# EasyDriver_v45.net
KiCad netlist of a schematic drawn in EAGLE
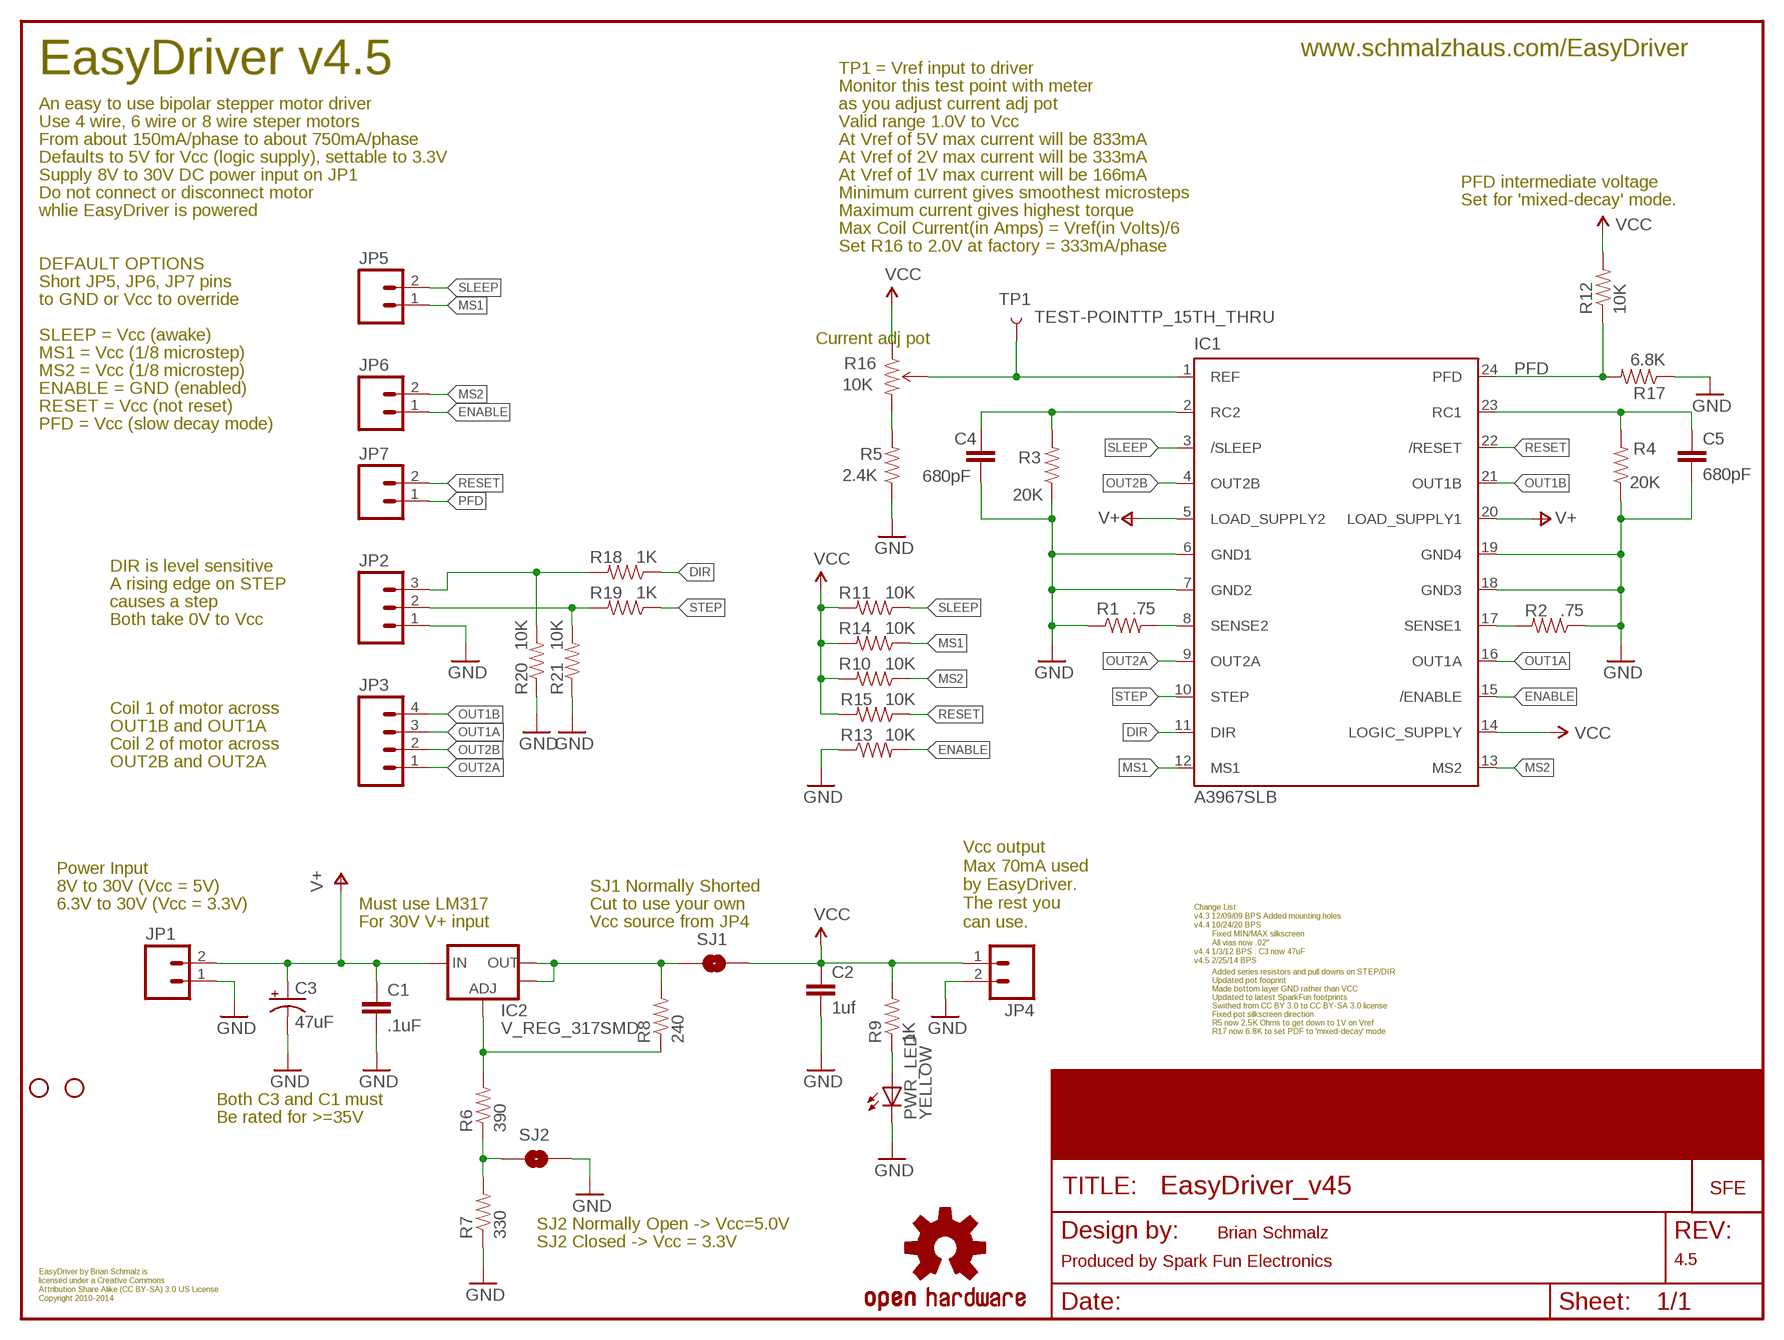
[diagram p0: schematic, sheet 1]

(export (version "E")
  (design (tool "Eeschema 10.0.6"))
  (components
    (comp (ref "C1")
      (value ".1uF")
      (footprint "eagle-import:0603-CAP")
      (libsource (lib "eagle-import") (part "CAP0603-CAP"))
    )
    (comp (ref "C2")
      (value "1uf")
      (footprint "eagle-import:0603-CAP")
      (libsource (lib "eagle-import") (part "CAP0603-CAP"))
    )
    (comp (ref "C3")
      (value "47uF")
      (footprint "eagle-import:PANASONIC_D")
      (libsource (lib "eagle-import") (part "CPOL-USD"))
    )
    (comp (ref "C4")
      (value "680pF")
      (footprint "eagle-import:0603-CAP")
      (libsource (lib "eagle-import") (part "CAP0603-CAP"))
    )
    (comp (ref "C5")
      (value "680pF")
      (footprint "eagle-import:0603-CAP")
      (libsource (lib "eagle-import") (part "CAP0603-CAP"))
    )
    (comp (ref "FRAME2")
      (value "FRAME-LETTER")
      (footprint "eagle-import:CREATIVE_COMMONS")
      (libsource (lib "eagle-import") (part "FRAME-LETTER"))
    )
    (comp (ref "IC1")
      (value "A3967SLB")
      (footprint "eagle-import:SO24W")
      (libsource (lib "eagle-import") (part "A3967SLB"))
    )
    (comp (ref "IC2")
      (value "V_REG_317SMD")
      (footprint "eagle-import:SOT223")
      (libsource (lib "eagle-import") (part "V_REG_317SMD"))
    )
    (comp (ref "JP1")
      (value "M021X02_NO_SILK")
      (footprint "eagle-import:1X02_NO_SILK")
      (libsource (lib "eagle-import") (part "M021X02_NO_SILK"))
    )
    (comp (ref "JP2")
      (value "M031X03_NO_SILK")
      (footprint "eagle-import:1X03_NO_SILK")
      (libsource (lib "eagle-import") (part "M031X03_NO_SILK"))
    )
    (comp (ref "JP3")
      (value "M041X04_NO_SILK")
      (footprint "eagle-import:1X04_NO_SILK")
      (libsource (lib "eagle-import") (part "M041X04_NO_SILK"))
    )
    (comp (ref "JP4")
      (value "M021X02_NO_SILK")
      (footprint "eagle-import:1X02_NO_SILK")
      (libsource (lib "eagle-import") (part "M021X02_NO_SILK"))
    )
    (comp (ref "JP5")
      (value "M021X02_NO_SILK")
      (footprint "eagle-import:1X02_NO_SILK")
      (libsource (lib "eagle-import") (part "M021X02_NO_SILK"))
    )
    (comp (ref "JP6")
      (value "M021X02_NO_SILK")
      (footprint "eagle-import:1X02_NO_SILK")
      (libsource (lib "eagle-import") (part "M021X02_NO_SILK"))
    )
    (comp (ref "JP7")
      (value "M021X02_NO_SILK")
      (footprint "eagle-import:1X02_NO_SILK")
      (libsource (lib "eagle-import") (part "M021X02_NO_SILK"))
    )
    (comp (ref "JP8")
      (value "STAND-OFF")
      (footprint "eagle-import:STAND-OFF")
      (libsource (lib "eagle-import") (part "STAND-OFF"))
    )
    (comp (ref "JP9")
      (value "STAND-OFF")
      (footprint "eagle-import:STAND-OFF")
      (libsource (lib "eagle-import") (part "STAND-OFF"))
    )
    (comp (ref "LOGO1")
      (value "OSHW-LOGOS")
      (footprint "eagle-import:OSHW-LOGO-S")
      (libsource (lib "eagle-import") (part "OSHW-LOGOS"))
    )
    (comp (ref "PWR_LED")
      (value "YELLOW")
      (footprint "eagle-import:LED-0603")
      (libsource (lib "eagle-import") (part "LED-YELLOW0603"))
    )
    (comp (ref "R1")
      (value ".75")
      (footprint "eagle-import:0805")
      (libsource (lib "eagle-import") (part "RESISTOR0805-RES"))
    )
    (comp (ref "R2")
      (value ".75")
      (footprint "eagle-import:0805")
      (libsource (lib "eagle-import") (part "RESISTOR0805-RES"))
    )
    (comp (ref "R3")
      (value "20K")
      (footprint "eagle-import:0603-RES")
      (libsource (lib "eagle-import") (part "RESISTOR0603"))
    )
    (comp (ref "R4")
      (value "20K")
      (footprint "eagle-import:0603-RES")
      (libsource (lib "eagle-import") (part "RESISTOR0603"))
    )
    (comp (ref "R5")
      (value "2.4K")
      (footprint "eagle-import:0603-RES")
      (libsource (lib "eagle-import") (part "RESISTOR0603"))
    )
    (comp (ref "R6")
      (value "390")
      (footprint "eagle-import:0603-RES")
      (libsource (lib "eagle-import") (part "RESISTOR0603"))
    )
    (comp (ref "R7")
      (value "330")
      (footprint "eagle-import:0603-RES")
      (libsource (lib "eagle-import") (part "RESISTOR0603"))
    )
    (comp (ref "R8")
      (value "240")
      (footprint "eagle-import:0603-RES")
      (libsource (lib "eagle-import") (part "RESISTOR0603"))
    )
    (comp (ref "R9")
      (value "1K")
      (footprint "eagle-import:0603-RES")
      (libsource (lib "eagle-import") (part "RESISTOR0603"))
    )
    (comp (ref "R10")
      (value "10K")
      (footprint "eagle-import:0603-RES")
      (libsource (lib "eagle-import") (part "RESISTOR0603"))
    )
    (comp (ref "R11")
      (value "10K")
      (footprint "eagle-import:0603-RES")
      (libsource (lib "eagle-import") (part "RESISTOR0603"))
    )
    (comp (ref "R12")
      (value "10K")
      (footprint "eagle-import:0603-RES")
      (libsource (lib "eagle-import") (part "RESISTOR0603"))
    )
    (comp (ref "R13")
      (value "10K")
      (footprint "eagle-import:0603-RES")
      (libsource (lib "eagle-import") (part "RESISTOR0603"))
    )
    (comp (ref "R14")
      (value "10K")
      (footprint "eagle-import:0603-RES")
      (libsource (lib "eagle-import") (part "RESISTOR0603"))
    )
    (comp (ref "R15")
      (value "10K")
      (footprint "eagle-import:0603-RES")
      (libsource (lib "eagle-import") (part "RESISTOR0603"))
    )
    (comp (ref "R16")
      (value "10K")
      (footprint "eagle-import:TRIMPOT-3MM-2")
      (libsource (lib "eagle-import") (part "TRIMPOT3MM-2"))
    )
    (comp (ref "R17")
      (value "6.8K")
      (footprint "eagle-import:0603-RES")
      (libsource (lib "eagle-import") (part "RESISTOR0603"))
    )
    (comp (ref "R18")
      (value "1K")
      (footprint "eagle-import:0603-RES")
      (libsource (lib "eagle-import") (part "RESISTOR0603"))
    )
    (comp (ref "R19")
      (value "1K")
      (footprint "eagle-import:0603-RES")
      (libsource (lib "eagle-import") (part "RESISTOR0603"))
    )
    (comp (ref "R20")
      (value "10K")
      (footprint "eagle-import:0603-RES")
      (libsource (lib "eagle-import") (part "RESISTOR0603"))
    )
    (comp (ref "R21")
      (value "10K")
      (footprint "eagle-import:0603-RES")
      (libsource (lib "eagle-import") (part "RESISTOR0603"))
    )
    (comp (ref "SJ1")
      (value "SOLDERJUMPERTRACE")
      (footprint "eagle-import:SJ_2S-TRACE")
      (libsource (lib "eagle-import") (part "SOLDERJUMPERTRACE"))
    )
    (comp (ref "SJ2")
      (value "SOLDERJUMPERNO")
      (footprint "eagle-import:SJ_2S-NO")
      (libsource (lib "eagle-import") (part "SOLDERJUMPERNO"))
    )
    (comp (ref "TP1")
      (value "TEST-POINTTP_15TH_THRU")
      (footprint "eagle-import:TP_15TH")
      (libsource (lib "eagle-import") (part "TEST-POINTTP_15TH_THRU"))
    )
    (comp (ref "U$2")
      (value "LOGO-SFENEW")
      (footprint "eagle-import:SFE-NEW-WEBLOGO")
      (libsource (lib "eagle-import") (part "LOGO-SFENEW"))
    )
  )
  (nets
    (net (code "1") (name "DIR") (class "Default")
      (node (ref "IC1") (pin "11") (pinfunction "DIR_11") (pintype "power_in"))
      (node (ref "R18") (pin "1") (pinfunction "1_1") (pintype "passive"))
    )
    (net (code "2") (name "ENABLE") (class "Default")
      (node (ref "IC1") (pin "15") (pinfunction "/ENABLE_15") (pintype "tri_state"))
      (node (ref "JP6") (pin "1") (pinfunction "1_1") (pintype "passive"))
      (node (ref "R13") (pin "2") (pinfunction "2_2") (pintype "passive"))
    )
    (net (code "3") (name "GND") (class "Default")
      (node (ref "C1") (pin "2") (pinfunction "2_2") (pintype "passive"))
      (node (ref "C2") (pin "2") (pinfunction "2_2") (pintype "passive"))
      (node (ref "C3") (pin "-") (pinfunction "-_-") (pintype "passive"))
      (node (ref "C4") (pin "2") (pinfunction "2_2") (pintype "passive"))
      (node (ref "C5") (pin "2") (pinfunction "2_2") (pintype "passive"))
      (node (ref "IC1") (pin "18") (pinfunction "GND3_18") (pintype "tri_state"))
      (node (ref "IC1") (pin "19") (pinfunction "GND4_19") (pintype "tri_state"))
      (node (ref "IC1") (pin "6") (pinfunction "GND1_6") (pintype "passive"))
      (node (ref "IC1") (pin "7") (pinfunction "GND2_7") (pintype "output"))
      (node (ref "JP1") (pin "1") (pinfunction "1_1") (pintype "passive"))
      (node (ref "JP2") (pin "1") (pinfunction "1_1") (pintype "passive"))
      (node (ref "JP4") (pin "2") (pinfunction "2_2") (pintype "passive"))
      (node (ref "PWR_LED") (pin "C") (pinfunction "C_C") (pintype "passive"))
      (node (ref "R1") (pin "1") (pinfunction "1_1") (pintype "passive"))
      (node (ref "R13") (pin "1") (pinfunction "1_1") (pintype "passive"))
      (node (ref "R17") (pin "1") (pinfunction "1_1") (pintype "passive"))
      (node (ref "R2") (pin "1") (pinfunction "1_1") (pintype "passive"))
      (node (ref "R20") (pin "1") (pinfunction "1_1") (pintype "passive"))
      (node (ref "R21") (pin "1") (pinfunction "1_1") (pintype "passive"))
      (node (ref "R3") (pin "1") (pinfunction "1_1") (pintype "passive"))
      (node (ref "R4") (pin "1") (pinfunction "1_1") (pintype "passive"))
      (node (ref "R5") (pin "1") (pinfunction "1_1") (pintype "passive"))
      (node (ref "R7") (pin "1") (pinfunction "1_1") (pintype "passive"))
      (node (ref "SJ2") (pin "2") (pinfunction "2_2") (pintype "passive"))
    )
    (net (code "4") (name "MS1") (class "Default")
      (node (ref "IC1") (pin "12") (pinfunction "MS1_12") (pintype "output"))
      (node (ref "JP5") (pin "1") (pinfunction "1_1") (pintype "passive"))
      (node (ref "R14") (pin "1") (pinfunction "1_1") (pintype "passive"))
    )
    (net (code "5") (name "MS2") (class "Default")
      (node (ref "IC1") (pin "13") (pinfunction "MS2_13") (pintype "tri_state"))
      (node (ref "JP6") (pin "2") (pinfunction "2_2") (pintype "passive"))
      (node (ref "R10") (pin "1") (pinfunction "1_1") (pintype "passive"))
    )
    (net (code "6") (name "Net-(IC1-RC1)") (class "Default")
      (node (ref "C5") (pin "1") (pinfunction "1_1") (pintype "passive"))
      (node (ref "IC1") (pin "23") (pinfunction "RC1_23") (pintype "tri_state"))
      (node (ref "R4") (pin "2") (pinfunction "2_2") (pintype "passive"))
    )
    (net (code "7") (name "Net-(IC1-RC2)") (class "Default")
      (node (ref "C4") (pin "1") (pinfunction "1_1") (pintype "passive"))
      (node (ref "IC1") (pin "2") (pinfunction "RC2_2") (pintype "input"))
      (node (ref "R3") (pin "2") (pinfunction "2_2") (pintype "passive"))
    )
    (net (code "8") (name "Net-(IC1-REF)") (class "Default")
      (node (ref "IC1") (pin "1") (pinfunction "REF_1") (pintype "power_in"))
      (node (ref "R16") (pin "2") (pinfunction "WIPER_2") (pintype "passive"))
      (node (ref "TP1") (pin "P$1") (pinfunction "1_P$1") (pintype "bidirectional"))
    )
    (net (code "9") (name "Net-(IC1-SENSE1)") (class "Default")
      (node (ref "IC1") (pin "17") (pinfunction "SENSE1_17") (pintype "tri_state"))
      (node (ref "R2") (pin "2") (pinfunction "2_2") (pintype "passive"))
    )
    (net (code "10") (name "Net-(IC1-SENSE2)") (class "Default")
      (node (ref "IC1") (pin "8") (pinfunction "SENSE2_8") (pintype "input"))
      (node (ref "R1") (pin "2") (pinfunction "2_2") (pintype "passive"))
    )
    (net (code "11") (name "Net-(IC2-ADJ)") (class "Default")
      (node (ref "IC2") (pin "1") (pinfunction "ADJ_1") (pintype "input"))
      (node (ref "R6") (pin "2") (pinfunction "2_2") (pintype "passive"))
      (node (ref "R8") (pin "1") (pinfunction "1_1") (pintype "passive"))
    )
    (net (code "12") (name "Net-(IC2-OUT-Pad2)") (class "Default")
      (node (ref "IC2") (pin "2") (pinfunction "OUT_2") (pintype "output"))
      (node (ref "IC2") (pin "4") (pinfunction "OUT_4") (pintype "output"))
      (node (ref "R8") (pin "2") (pinfunction "2_2") (pintype "passive"))
      (node (ref "SJ1") (pin "1") (pinfunction "1_1") (pintype "passive"))
    )
    (net (code "13") (name "Net-(JP2-Pad2)") (class "Default")
      (node (ref "JP2") (pin "2") (pinfunction "2_2") (pintype "passive"))
      (node (ref "R19") (pin "2") (pinfunction "2_2") (pintype "passive"))
      (node (ref "R21") (pin "2") (pinfunction "2_2") (pintype "passive"))
    )
    (net (code "14") (name "Net-(JP2-Pad3)") (class "Default")
      (node (ref "JP2") (pin "3") (pinfunction "3_3") (pintype "passive"))
      (node (ref "R18") (pin "2") (pinfunction "2_2") (pintype "passive"))
      (node (ref "R20") (pin "2") (pinfunction "2_2") (pintype "passive"))
    )
    (net (code "15") (name "Net-(PWR_LED-PadA)") (class "Default")
      (node (ref "PWR_LED") (pin "A") (pinfunction "A_A") (pintype "passive"))
      (node (ref "R9") (pin "1") (pinfunction "1_1") (pintype "passive"))
    )
    (net (code "16") (name "Net-(R6-Pad1)") (class "Default")
      (node (ref "R6") (pin "1") (pinfunction "1_1") (pintype "passive"))
      (node (ref "R7") (pin "2") (pinfunction "2_2") (pintype "passive"))
      (node (ref "SJ2") (pin "1") (pinfunction "1_1") (pintype "passive"))
    )
    (net (code "17") (name "Net-(R16-CW)") (class "Default")
      (node (ref "R16") (pin "3") (pinfunction "CW_3") (pintype "passive"))
      (node (ref "R5") (pin "2") (pinfunction "2_2") (pintype "passive"))
    )
    (net (code "18") (name "OUT1A") (class "Default")
      (node (ref "IC1") (pin "16") (pinfunction "OUT1A_16") (pintype "tri_state"))
      (node (ref "JP3") (pin "3") (pinfunction "3_3") (pintype "passive"))
    )
    (net (code "19") (name "OUT1B") (class "Default")
      (node (ref "IC1") (pin "21") (pinfunction "OUT1B_21") (pintype "tri_state"))
      (node (ref "JP3") (pin "4") (pinfunction "4_4") (pintype "passive"))
    )
    (net (code "20") (name "OUT2A") (class "Default")
      (node (ref "IC1") (pin "9") (pinfunction "OUT2A_9") (pintype "power_in"))
      (node (ref "JP3") (pin "1") (pinfunction "1_1") (pintype "passive"))
    )
    (net (code "21") (name "OUT2B") (class "Default")
      (node (ref "IC1") (pin "4") (pinfunction "OUT2B_4") (pintype "passive"))
      (node (ref "JP3") (pin "2") (pinfunction "2_2") (pintype "passive"))
    )
    (net (code "22") (name "PFD") (class "Default")
      (node (ref "IC1") (pin "24") (pinfunction "PFD_24") (pintype "tri_state"))
      (node (ref "JP7") (pin "1") (pinfunction "1_1") (pintype "passive"))
      (node (ref "R12") (pin "1") (pinfunction "1_1") (pintype "passive"))
      (node (ref "R17") (pin "2") (pinfunction "2_2") (pintype "passive"))
    )
    (net (code "23") (name "RESET") (class "Default")
      (node (ref "IC1") (pin "22") (pinfunction "/RESET_22") (pintype "tri_state"))
      (node (ref "JP7") (pin "2") (pinfunction "2_2") (pintype "passive"))
      (node (ref "R15") (pin "1") (pinfunction "1_1") (pintype "passive"))
    )
    (net (code "24") (name "SLEEP") (class "Default")
      (node (ref "IC1") (pin "3") (pinfunction "/SLEEP_3") (pintype "passive"))
      (node (ref "JP5") (pin "2") (pinfunction "2_2") (pintype "passive"))
      (node (ref "R11") (pin "1") (pinfunction "1_1") (pintype "passive"))
    )
    (net (code "25") (name "STEP") (class "Default")
      (node (ref "IC1") (pin "10") (pinfunction "STEP_10") (pintype "power_in"))
      (node (ref "R19") (pin "1") (pinfunction "1_1") (pintype "passive"))
    )
    (net (code "26") (name "V+") (class "Default")
      (node (ref "C1") (pin "1") (pinfunction "1_1") (pintype "passive"))
      (node (ref "C3") (pin "+") (pinfunction "+_+") (pintype "passive"))
      (node (ref "IC1") (pin "20") (pinfunction "LOAD_SUPPLY1_20") (pintype "tri_state"))
      (node (ref "IC1") (pin "5") (pinfunction "LOAD_SUPPLY2_5") (pintype "passive"))
      (node (ref "IC2") (pin "3") (pinfunction "IN_3") (pintype "input"))
      (node (ref "JP1") (pin "2") (pinfunction "2_2") (pintype "passive"))
    )
    (net (code "27") (name "VCC") (class "Default")
      (node (ref "C2") (pin "1") (pinfunction "1_1") (pintype "passive"))
      (node (ref "IC1") (pin "14") (pinfunction "LOGIC_SUPPLY_14") (pintype "tri_state"))
      (node (ref "JP4") (pin "1") (pinfunction "1_1") (pintype "passive"))
      (node (ref "R10") (pin "2") (pinfunction "2_2") (pintype "passive"))
      (node (ref "R11") (pin "2") (pinfunction "2_2") (pintype "passive"))
      (node (ref "R12") (pin "2") (pinfunction "2_2") (pintype "passive"))
      (node (ref "R14") (pin "2") (pinfunction "2_2") (pintype "passive"))
      (node (ref "R15") (pin "2") (pinfunction "2_2") (pintype "passive"))
      (node (ref "R16") (pin "1") (pinfunction "CCW_1") (pintype "passive"))
      (node (ref "R9") (pin "2") (pinfunction "2_2") (pintype "passive"))
      (node (ref "SJ1") (pin "2") (pinfunction "2_2") (pintype "passive"))
    )
  )
)
